# MCU_NODE.net
KiCad netlist of a schematic drawn in Altium Designer
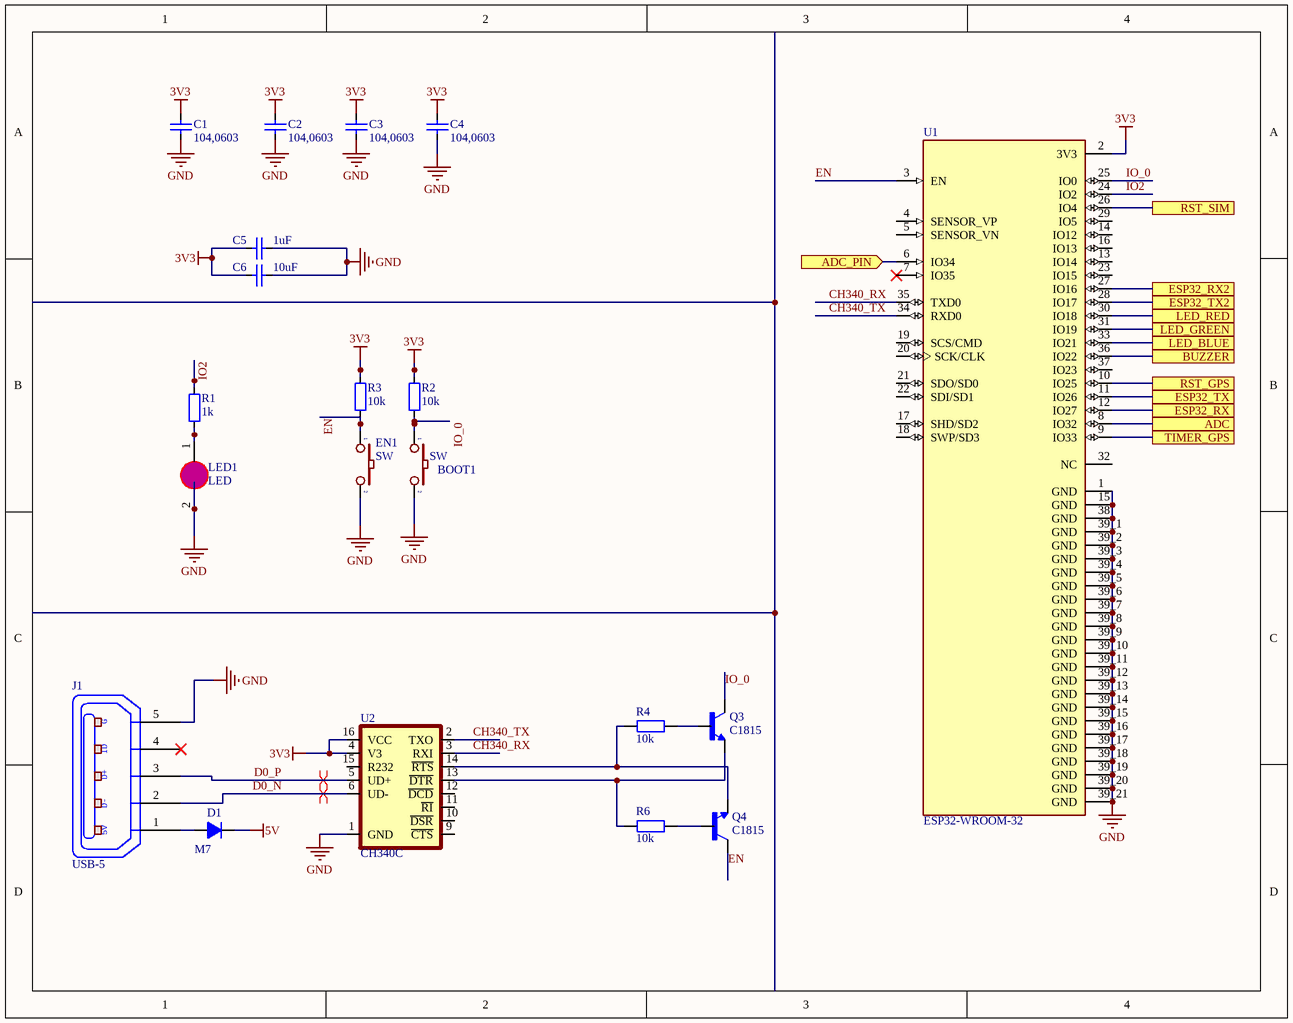
[diagram p0: MCU_NODE.SchDoc]

(export (version "E")
  (design (tool "Eeschema 10.0.6"))
  (components
    (comp (ref "BOOT1")
      (value "SW")
      (footprint "SW-SMD")
      (description "Switch button 2 pin")
      (libsource (lib "My Library") (part "SW2"))
    )
    (comp (ref "C1")
      (value "104,0603")
      (footprint "CAP_0603")
      (description "Capacitor")
      (fields (field (name "PUBLISHER") "Altium Limited"))
      (libsource (lib "My Library") (part "CapSMD"))
    )
    (comp (ref "C2")
      (value "104,0603")
      (footprint "CAP_0603")
      (description "Capacitor")
      (fields (field (name "PUBLISHER") "Altium Limited"))
      (libsource (lib "My Library") (part "CapSMD"))
    )
    (comp (ref "C3")
      (value "104,0603")
      (footprint "CAP_0603")
      (description "Capacitor")
      (fields (field (name "PUBLISHER") "Altium Limited"))
      (libsource (lib "My Library") (part "CapSMD"))
    )
    (comp (ref "C4")
      (value "104,0603")
      (footprint "CAP_0603")
      (description "Capacitor")
      (fields (field (name "PUBLISHER") "Altium Limited"))
      (libsource (lib "My Library") (part "CapSMD"))
    )
    (comp (ref "C5")
      (value "1uF")
      (footprint "CAP_0603")
      (description "Capacitor")
      (fields (field (name "PUBLISHER") "Altium Limited"))
      (libsource (lib "My Library") (part "CapSMD"))
    )
    (comp (ref "C6")
      (value "10uF")
      (footprint "CAP_0603")
      (description "Capacitor")
      (fields (field (name "PUBLISHER") "Altium Limited"))
      (libsource (lib "My Library") (part "CapSMD"))
    )
    (comp (ref "D1")
      (value "M7")
      (footprint "SMA")
      (description "Diode 1A")
      (libsource (lib "Main") (part "D1A"))
    )
    (comp (ref "EN1")
      (value "SW")
      (footprint "SW-SMD")
      (description "Switch button 2 pin")
      (libsource (lib "My Library") (part "SW2"))
    )
    (comp (ref "J1")
      (value "USB-5")
      (footprint "USB-M1")
      (fields
        (field (name "MANUFACTURER") "FCI")
        (field (name "MANUFACTURER PART NUMBER") "10118193-0001LF")
        (field (name ".CREATOR") "MM")
        (field (name ".CHECKED PCB") "RF")
        (field (name ".CHECKED SCH") "MM")
      )
      (libsource (lib "My Library 2") (part "USB-5"))
    )
    (comp (ref "LED1")
      (value "LED")
      (footprint "LED0805")
      (description "LED SMD 0805")
      (libsource (lib "My Library 2") (part "LED0805"))
    )
    (comp (ref "Q3")
      (value "C1815")
      (footprint "SOT95P240X97-3N")
      (description "Bipolar (BJT) Transistor NPN 45V 500mA 100MHz 250mW Surface Mount TO-236AB")
      (fields (field (name "MP") "BC817") (field (name "MF") "Rectron"))
      (libsource (lib "") (part "BC817_1"))
    )
    (comp (ref "Q4")
      (value "C1815")
      (footprint "SOT95P240X97-3N")
      (description "Bipolar (BJT) Transistor NPN 45V 500mA 100MHz 250mW Surface Mount TO-236AB")
      (fields (field (name "MP") "BC817") (field (name "MF") "Rectron"))
      (libsource (lib "BC817") (part "BC817"))
    )
    (comp (ref "R1")
      (value "1k")
      (footprint "RES-SMD-0603")
      (description "Resistor SMD")
      (fields
        (field (name "MANUFACTURER") "Generic Components")
        (field (name "PUBLISHER") "Altium Hobart Technology Centre")
      )
      (libsource (lib "My Library") (part "Resistor - SMD"))
    )
    (comp (ref "R2")
      (value "10k")
      (footprint "RES-SMD-0603")
      (description "Resistor SMD")
      (fields
        (field (name "MANUFACTURER") "Generic Components")
        (field (name "PUBLISHER") "Altium Hobart Technology Centre")
      )
      (libsource (lib "My Library") (part "Resistor - SMD"))
    )
    (comp (ref "R3")
      (value "10k")
      (footprint "RES-SMD-0603")
      (description "Resistor SMD")
      (fields
        (field (name "MANUFACTURER") "Generic Components")
        (field (name "PUBLISHER") "Altium Hobart Technology Centre")
      )
      (libsource (lib "My Library") (part "Resistor - SMD"))
    )
    (comp (ref "R4")
      (value "10k")
      (footprint "RES-SMD-0603")
      (description "Resistor SMD")
      (fields
        (field (name "MANUFACTURER") "Generic Components")
        (field (name "PUBLISHER") "Altium Hobart Technology Centre")
      )
      (libsource (lib "My Library") (part "Resistor - SMD"))
    )
    (comp (ref "R6")
      (value "10k")
      (footprint "RES-SMD-0603")
      (description "Resistor SMD")
      (fields
        (field (name "MANUFACTURER") "Generic Components")
        (field (name "PUBLISHER") "Altium Hobart Technology Centre")
      )
      (libsource (lib "My Library") (part "Resistor - SMD"))
    )
    (comp (ref "U1")
      (value "ESP32-WROOM-32")
      (footprint "MODULE_ESP32-WROOM-32")
      (fields (field (name "MF") "Espressif Systems"))
      (libsource (lib "ESP32-WROOM-32") (part "ESP32-WROOM-32"))
    )
    (comp (ref "U2")
      (value "CH340C")
      (footprint "SOP-16")
      (description "USB to serial chip CH340")
      (fields (field (name "MF") "WCH"))
      (libsource (lib "My Library") (part "CH340C"))
    )
  )
  (nets
    (net (code "1") (name "/ADC") (class "Default")
      (node (ref "U1") (pin "8") (pinfunction "IO32_8") (pintype "bidirectional"))
    )
    (net (code "2") (name "/ADC_PIN") (class "Default")
      (node (ref "U1") (pin "6") (pinfunction "IO34_6") (pintype "input"))
    )
    (net (code "3") (name "/BUZZER") (class "Default")
      (node (ref "U1") (pin "36") (pinfunction "IO22_36") (pintype "bidirectional"))
    )
    (net (code "4") (name "/CH340_RX") (class "Default")
      (node (ref "U1") (pin "35") (pinfunction "TXD0_35") (pintype "bidirectional"))
      (node (ref "U2") (pin "3") (pinfunction "RXI_3") (pintype "bidirectional"))
    )
    (net (code "5") (name "/CH340_TX") (class "Default")
      (node (ref "U1") (pin "34") (pinfunction "RXD0_34") (pintype "bidirectional"))
      (node (ref "U2") (pin "2") (pinfunction "TXO_2") (pintype "bidirectional"))
    )
    (net (code "6") (name "/D0_N") (class "Default")
      (node (ref "J1") (pin "2") (pinfunction "P2_2") (pintype "passive"))
      (node (ref "U2") (pin "6") (pinfunction "UD-_6") (pintype "bidirectional"))
    )
    (net (code "7") (name "/D0_P") (class "Default")
      (node (ref "J1") (pin "3") (pinfunction "P3_3") (pintype "passive"))
      (node (ref "U2") (pin "5") (pinfunction "UD+_5") (pintype "bidirectional"))
    )
    (net (code "8") (name "/EN") (class "Default")
      (node (ref "EN1") (pin "1") (pinfunction "1_1") (pintype "passive"))
      (node (ref "Q4") (pin "3") (pinfunction "C_3") (pintype "passive"))
      (node (ref "R3") (pin "2") (pinfunction "2_2") (pintype "passive"))
      (node (ref "U1") (pin "3") (pinfunction "EN_3") (pintype "input"))
    )
    (net (code "9") (name "/ESP32_RX") (class "Default")
      (node (ref "U1") (pin "12") (pinfunction "IO27_12") (pintype "bidirectional"))
    )
    (net (code "10") (name "/ESP32_RX2") (class "Default")
      (node (ref "U1") (pin "27") (pinfunction "IO16_27") (pintype "bidirectional"))
    )
    (net (code "11") (name "/ESP32_TX") (class "Default")
      (node (ref "U1") (pin "11") (pinfunction "IO26_11") (pintype "bidirectional"))
    )
    (net (code "12") (name "/ESP32_TX2") (class "Default")
      (node (ref "U1") (pin "28") (pinfunction "IO17_28") (pintype "bidirectional"))
    )
    (net (code "13") (name "/IO2") (class "Default")
      (node (ref "R1") (pin "1") (pinfunction "1_1") (pintype "passive"))
      (node (ref "U1") (pin "24") (pinfunction "IO2_24") (pintype "bidirectional"))
    )
    (net (code "14") (name "/IO_0") (class "Default")
      (node (ref "BOOT1") (pin "1") (pinfunction "1_1") (pintype "passive"))
      (node (ref "Q3") (pin "3") (pinfunction "C_3") (pintype "passive"))
      (node (ref "R2") (pin "2") (pinfunction "2_2") (pintype "passive"))
      (node (ref "U1") (pin "25") (pinfunction "IO0_25") (pintype "bidirectional"))
    )
    (net (code "15") (name "/LED_BLUE") (class "Default")
      (node (ref "U1") (pin "33") (pinfunction "IO21_33") (pintype "bidirectional"))
    )
    (net (code "16") (name "/LED_GREEN") (class "Default")
      (node (ref "U1") (pin "31") (pinfunction "IO19_31") (pintype "bidirectional"))
    )
    (net (code "17") (name "/LED_RED") (class "Default")
      (node (ref "U1") (pin "30") (pinfunction "IO18_30") (pintype "bidirectional"))
    )
    (net (code "18") (name "/RST_GPS") (class "Default")
      (node (ref "U1") (pin "10") (pinfunction "IO25_10") (pintype "bidirectional"))
    )
    (net (code "19") (name "/RST_SIM") (class "Default")
      (node (ref "U1") (pin "26") (pinfunction "IO4_26") (pintype "bidirectional"))
    )
    (net (code "20") (name "/TIMER_GPS") (class "Default")
      (node (ref "U1") (pin "9") (pinfunction "IO33_9") (pintype "bidirectional"))
    )
    (net (code "21") (name "3V3") (class "Default")
      (node (ref "C1") (pin "2") (pinfunction "2_2") (pintype "passive"))
      (node (ref "C2") (pin "2") (pinfunction "2_2") (pintype "passive"))
      (node (ref "C3") (pin "2") (pinfunction "2_2") (pintype "passive"))
      (node (ref "C4") (pin "2") (pinfunction "2_2") (pintype "passive"))
      (node (ref "C5") (pin "1") (pinfunction "1_1") (pintype "passive"))
      (node (ref "C6") (pin "1") (pinfunction "1_1") (pintype "passive"))
      (node (ref "R2") (pin "1") (pinfunction "1_1") (pintype "passive"))
      (node (ref "R3") (pin "1") (pinfunction "1_1") (pintype "passive"))
      (node (ref "U1") (pin "2") (pinfunction "3V3_2") (pintype "power_in"))
      (node (ref "U2") (pin "16") (pinfunction "VCC_16") (pintype "bidirectional"))
      (node (ref "U2") (pin "4") (pinfunction "V3_4") (pintype "bidirectional"))
    )
    (net (code "22") (name "5V") (class "Default")
      (node (ref "D1") (pin "2") (pinfunction "K_2") (pintype "passive"))
    )
    (net (code "23") (name "GND") (class "Default")
      (node (ref "BOOT1") (pin "2") (pinfunction "2_2") (pintype "passive"))
      (node (ref "C1") (pin "1") (pinfunction "1_1") (pintype "passive"))
      (node (ref "C2") (pin "1") (pinfunction "1_1") (pintype "passive"))
      (node (ref "C3") (pin "1") (pinfunction "1_1") (pintype "passive"))
      (node (ref "C4") (pin "1") (pinfunction "1_1") (pintype "passive"))
      (node (ref "C5") (pin "2") (pinfunction "2_2") (pintype "passive"))
      (node (ref "C6") (pin "2") (pinfunction "2_2") (pintype "passive"))
      (node (ref "EN1") (pin "2") (pinfunction "2_2") (pintype "passive"))
      (node (ref "J1") (pin "5") (pinfunction "P5_5") (pintype "passive"))
      (node (ref "LED1") (pin "2") (pinfunction "K_2") (pintype "passive"))
      (node (ref "U1") (pin "1") (pinfunction "GND_1") (pintype "power_in"))
      (node (ref "U1") (pin "15") (pinfunction "GND_15") (pintype "power_in"))
      (node (ref "U1") (pin "38") (pinfunction "GND_38") (pintype "power_in"))
      (node (ref "U1") (pin "39_1") (pinfunction "GND_39_1") (pintype "power_in"))
      (node (ref "U1") (pin "39_10") (pinfunction "GND_39_10") (pintype "power_in"))
      (node (ref "U1") (pin "39_11") (pinfunction "GND_39_11") (pintype "power_in"))
      (node (ref "U1") (pin "39_12") (pinfunction "GND_39_12") (pintype "power_in"))
      (node (ref "U1") (pin "39_13") (pinfunction "GND_39_13") (pintype "power_in"))
      (node (ref "U1") (pin "39_14") (pinfunction "GND_39_14") (pintype "power_in"))
      (node (ref "U1") (pin "39_15") (pinfunction "GND_39_15") (pintype "power_in"))
      (node (ref "U1") (pin "39_16") (pinfunction "GND_39_16") (pintype "power_in"))
      (node (ref "U1") (pin "39_17") (pinfunction "GND_39_17") (pintype "power_in"))
      (node (ref "U1") (pin "39_18") (pinfunction "GND_39_18") (pintype "power_in"))
      (node (ref "U1") (pin "39_19") (pinfunction "GND_39_19") (pintype "power_in"))
      (node (ref "U1") (pin "39_2") (pinfunction "GND_39_2") (pintype "power_in"))
      (node (ref "U1") (pin "39_20") (pinfunction "GND_39_20") (pintype "power_in"))
      (node (ref "U1") (pin "39_21") (pinfunction "GND_39_21") (pintype "power_in"))
      (node (ref "U1") (pin "39_3") (pinfunction "GND_39_3") (pintype "power_in"))
      (node (ref "U1") (pin "39_4") (pinfunction "GND_39_4") (pintype "power_in"))
      (node (ref "U1") (pin "39_5") (pinfunction "GND_39_5") (pintype "power_in"))
      (node (ref "U1") (pin "39_6") (pinfunction "GND_39_6") (pintype "power_in"))
      (node (ref "U1") (pin "39_7") (pinfunction "GND_39_7") (pintype "power_in"))
      (node (ref "U1") (pin "39_8") (pinfunction "GND_39_8") (pintype "power_in"))
      (node (ref "U1") (pin "39_9") (pinfunction "GND_39_9") (pintype "power_in"))
      (node (ref "U2") (pin "1") (pinfunction "GND_1") (pintype "bidirectional"))
    )
    (net (code "24") (name "Net-(D1-A)") (class "Default")
      (node (ref "D1") (pin "1") (pinfunction "A_1") (pintype "passive"))
      (node (ref "J1") (pin "1") (pinfunction "P1_1") (pintype "passive"))
    )
    (net (code "25") (name "Net-(LED1-A)") (class "Default")
      (node (ref "LED1") (pin "1") (pinfunction "A_1") (pintype "passive"))
      (node (ref "R1") (pin "2") (pinfunction "2_2") (pintype "passive"))
    )
    (net (code "26") (name "Net-(Q3-B)") (class "Default")
      (node (ref "Q3") (pin "1") (pinfunction "B_1") (pintype "passive"))
      (node (ref "R4") (pin "2") (pinfunction "2_2") (pintype "passive"))
    )
    (net (code "27") (name "Net-(Q3-E)") (class "Default")
      (node (ref "Q3") (pin "2") (pinfunction "E_2") (pintype "passive"))
      (node (ref "R6") (pin "1") (pinfunction "1_1") (pintype "passive"))
      (node (ref "U2") (pin "13") (pinfunction "~{DTR}_13") (pintype "bidirectional"))
    )
    (net (code "28") (name "Net-(Q4-B)") (class "Default")
      (node (ref "Q4") (pin "1") (pinfunction "B_1") (pintype "passive"))
      (node (ref "R6") (pin "2") (pinfunction "2_2") (pintype "passive"))
    )
    (net (code "29") (name "Net-(Q4-E)") (class "Default")
      (node (ref "Q4") (pin "2") (pinfunction "E_2") (pintype "passive"))
      (node (ref "R4") (pin "1") (pinfunction "1_1") (pintype "passive"))
      (node (ref "U2") (pin "14") (pinfunction "~{RTS}_14") (pintype "bidirectional"))
    )
    (net (code "30") (name "unconnected-(J1-P4-Pad4)") (class "Default")
      (node (ref "J1") (pin "4") (pinfunction "P4_4") (pintype "passive+no_connect"))
    )
    (net (code "31") (name "unconnected-(U1-IO5-Pad29)") (class "Default")
      (node (ref "U1") (pin "29") (pinfunction "IO5_29") (pintype "bidirectional"))
    )
    (net (code "32") (name "unconnected-(U1-IO12-Pad14)") (class "Default")
      (node (ref "U1") (pin "14") (pinfunction "IO12_14") (pintype "bidirectional"))
    )
    (net (code "33") (name "unconnected-(U1-IO13-Pad16)") (class "Default")
      (node (ref "U1") (pin "16") (pinfunction "IO13_16") (pintype "bidirectional"))
    )
    (net (code "34") (name "unconnected-(U1-IO14-Pad13)") (class "Default")
      (node (ref "U1") (pin "13") (pinfunction "IO14_13") (pintype "bidirectional"))
    )
    (net (code "35") (name "unconnected-(U1-IO15-Pad23)") (class "Default")
      (node (ref "U1") (pin "23") (pinfunction "IO15_23") (pintype "bidirectional"))
    )
    (net (code "36") (name "unconnected-(U1-IO23-Pad37)") (class "Default")
      (node (ref "U1") (pin "37") (pinfunction "IO23_37") (pintype "bidirectional"))
    )
    (net (code "37") (name "unconnected-(U1-IO35-Pad7)") (class "Default")
      (node (ref "U1") (pin "7") (pinfunction "IO35_7") (pintype "input+no_connect"))
    )
    (net (code "38") (name "unconnected-(U1-NC-Pad32)") (class "Default")
      (node (ref "U1") (pin "32") (pinfunction "NC_32") (pintype "passive"))
    )
    (net (code "39") (name "unconnected-(U1-SCK{slash}CLK-Pad20)") (class "Default")
      (node (ref "U1") (pin "20") (pinfunction "SCK/CLK_20") (pintype "bidirectional"))
    )
    (net (code "40") (name "unconnected-(U1-SCS{slash}CMD-Pad19)") (class "Default")
      (node (ref "U1") (pin "19") (pinfunction "SCS/CMD_19") (pintype "bidirectional"))
    )
    (net (code "41") (name "unconnected-(U1-SDI{slash}SD1-Pad22)") (class "Default")
      (node (ref "U1") (pin "22") (pinfunction "SDI/SD1_22") (pintype "bidirectional"))
    )
    (net (code "42") (name "unconnected-(U1-SDO{slash}SD0-Pad21)") (class "Default")
      (node (ref "U1") (pin "21") (pinfunction "SDO/SD0_21") (pintype "bidirectional"))
    )
    (net (code "43") (name "unconnected-(U1-SENSOR_VN-Pad5)") (class "Default")
      (node (ref "U1") (pin "5") (pinfunction "SENSOR_VN_5") (pintype "input"))
    )
    (net (code "44") (name "unconnected-(U1-SENSOR_VP-Pad4)") (class "Default")
      (node (ref "U1") (pin "4") (pinfunction "SENSOR_VP_4") (pintype "input"))
    )
    (net (code "45") (name "unconnected-(U1-SHD{slash}SD2-Pad17)") (class "Default")
      (node (ref "U1") (pin "17") (pinfunction "SHD/SD2_17") (pintype "bidirectional"))
    )
    (net (code "46") (name "unconnected-(U1-SWP{slash}SD3-Pad18)") (class "Default")
      (node (ref "U1") (pin "18") (pinfunction "SWP/SD3_18") (pintype "bidirectional"))
    )
    (net (code "47") (name "unconnected-(U2-R232-Pad15)") (class "Default")
      (node (ref "U2") (pin "15") (pinfunction "R232_15") (pintype "bidirectional"))
    )
    (net (code "48") (name "unconnected-(U2-~{CTS}-Pad9)") (class "Default")
      (node (ref "U2") (pin "9") (pinfunction "~{CTS}_9") (pintype "bidirectional"))
    )
    (net (code "49") (name "unconnected-(U2-~{DCD}-Pad12)") (class "Default")
      (node (ref "U2") (pin "12") (pinfunction "~{DCD}_12") (pintype "bidirectional"))
    )
    (net (code "50") (name "unconnected-(U2-~{DSR}-Pad10)") (class "Default")
      (node (ref "U2") (pin "10") (pinfunction "~{DSR}_10") (pintype "bidirectional"))
    )
    (net (code "51") (name "unconnected-(U2-~{RI}-Pad11)") (class "Default")
      (node (ref "U2") (pin "11") (pinfunction "~{RI}_11") (pintype "bidirectional"))
    )
  )
)
